# zx81-keyboard.net
KiCad netlist of a schematic drawn in EAGLE
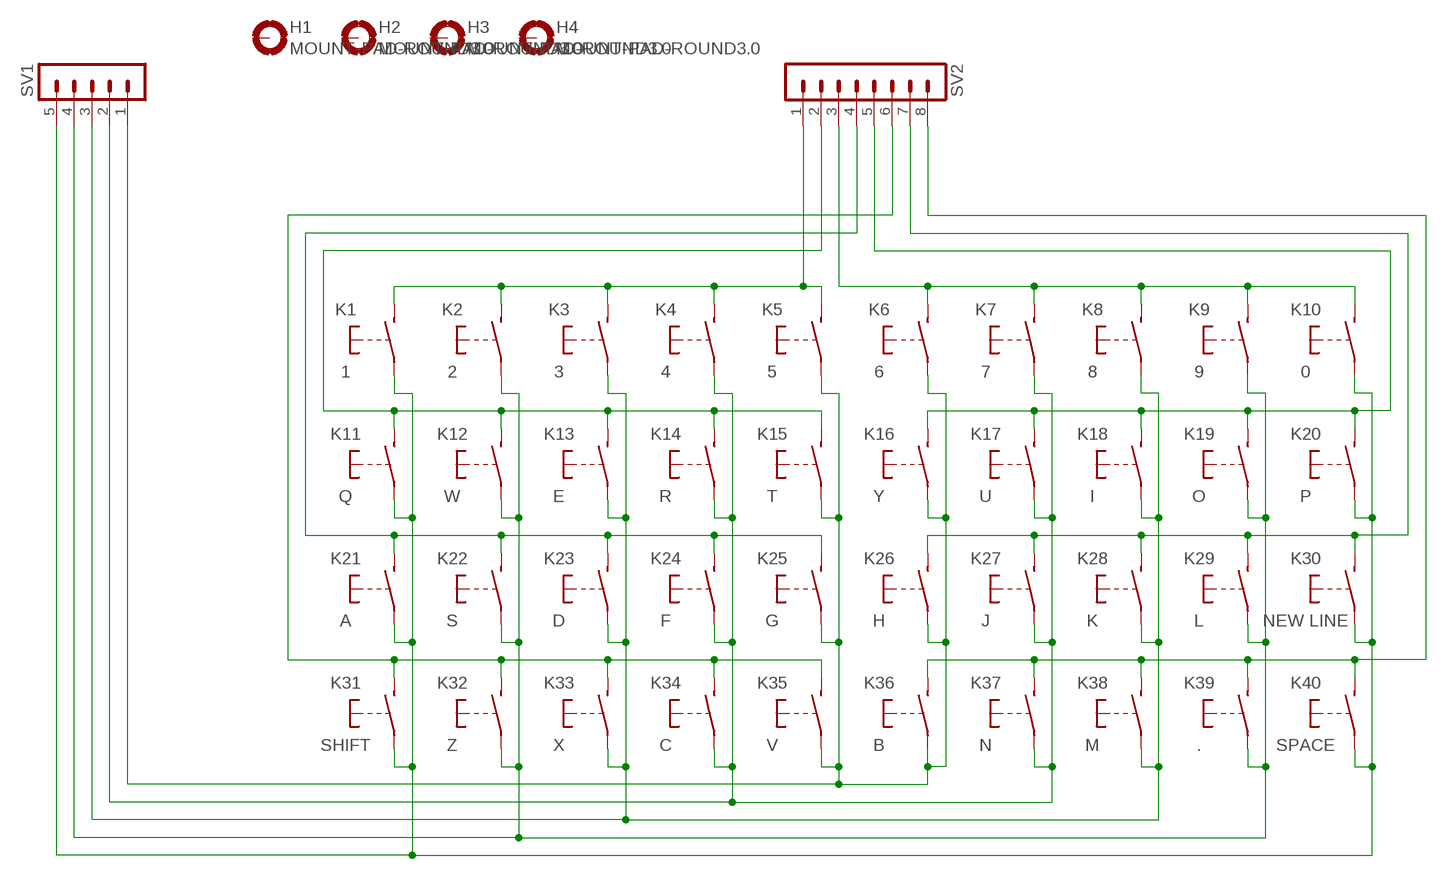
[diagram p0: schematic, sheet 1]

(export (version "E")
  (design (tool "Eeschema 10.0.6"))
  (components
    (comp (ref "H1")
      (value "MOUNT-PAD-ROUND3.0")
      (footprint "eagle-import:3,0-PAD")
      (libsource (lib "eagle-import") (part "MOUNT-PAD-ROUND3.0"))
    )
    (comp (ref "H2")
      (value "MOUNT-PAD-ROUND3.0")
      (footprint "eagle-import:3,0-PAD")
      (libsource (lib "eagle-import") (part "MOUNT-PAD-ROUND3.0"))
    )
    (comp (ref "H3")
      (value "MOUNT-PAD-ROUND3.0")
      (footprint "eagle-import:3,0-PAD")
      (libsource (lib "eagle-import") (part "MOUNT-PAD-ROUND3.0"))
    )
    (comp (ref "H4")
      (value "MOUNT-PAD-ROUND3.0")
      (footprint "eagle-import:3,0-PAD")
      (libsource (lib "eagle-import") (part "MOUNT-PAD-ROUND3.0"))
    )
    (comp (ref "K1")
      (value "1")
      (footprint "eagle-import:MARQUARTDT-6425")
      (libsource (lib "eagle-import") (part "MARQUART-6425"))
    )
    (comp (ref "K2")
      (value "2")
      (footprint "eagle-import:MARQUARTDT-6425")
      (libsource (lib "eagle-import") (part "MARQUART-6425"))
    )
    (comp (ref "K3")
      (value "3")
      (footprint "eagle-import:MARQUARTDT-6425")
      (libsource (lib "eagle-import") (part "MARQUART-6425"))
    )
    (comp (ref "K4")
      (value "4")
      (footprint "eagle-import:MARQUARTDT-6425")
      (libsource (lib "eagle-import") (part "MARQUART-6425"))
    )
    (comp (ref "K5")
      (value "5")
      (footprint "eagle-import:MARQUARTDT-6425")
      (libsource (lib "eagle-import") (part "MARQUART-6425"))
    )
    (comp (ref "K6")
      (value "6")
      (footprint "eagle-import:MARQUARTDT-6425")
      (libsource (lib "eagle-import") (part "MARQUART-6425"))
    )
    (comp (ref "K7")
      (value "7")
      (footprint "eagle-import:MARQUARTDT-6425")
      (libsource (lib "eagle-import") (part "MARQUART-6425"))
    )
    (comp (ref "K8")
      (value "8")
      (footprint "eagle-import:MARQUARTDT-6425")
      (libsource (lib "eagle-import") (part "MARQUART-6425"))
    )
    (comp (ref "K9")
      (value "9")
      (footprint "eagle-import:MARQUARTDT-6425")
      (libsource (lib "eagle-import") (part "MARQUART-6425"))
    )
    (comp (ref "K10")
      (value "0")
      (footprint "eagle-import:MARQUARTDT-6425")
      (libsource (lib "eagle-import") (part "MARQUART-6425"))
    )
    (comp (ref "K11")
      (value "Q")
      (footprint "eagle-import:MARQUARTDT-6425")
      (libsource (lib "eagle-import") (part "MARQUART-6425"))
    )
    (comp (ref "K12")
      (value "W")
      (footprint "eagle-import:MARQUARTDT-6425")
      (libsource (lib "eagle-import") (part "MARQUART-6425"))
    )
    (comp (ref "K13")
      (value "E")
      (footprint "eagle-import:MARQUARTDT-6425")
      (libsource (lib "eagle-import") (part "MARQUART-6425"))
    )
    (comp (ref "K14")
      (value "R")
      (footprint "eagle-import:MARQUARTDT-6425")
      (libsource (lib "eagle-import") (part "MARQUART-6425"))
    )
    (comp (ref "K15")
      (value "T")
      (footprint "eagle-import:MARQUARTDT-6425")
      (libsource (lib "eagle-import") (part "MARQUART-6425"))
    )
    (comp (ref "K16")
      (value "Y")
      (footprint "eagle-import:MARQUARTDT-6425")
      (libsource (lib "eagle-import") (part "MARQUART-6425"))
    )
    (comp (ref "K17")
      (value "U")
      (footprint "eagle-import:MARQUARTDT-6425")
      (libsource (lib "eagle-import") (part "MARQUART-6425"))
    )
    (comp (ref "K18")
      (value "I")
      (footprint "eagle-import:MARQUARTDT-6425")
      (libsource (lib "eagle-import") (part "MARQUART-6425"))
    )
    (comp (ref "K19")
      (value "O")
      (footprint "eagle-import:MARQUARTDT-6425")
      (libsource (lib "eagle-import") (part "MARQUART-6425"))
    )
    (comp (ref "K20")
      (value "P")
      (footprint "eagle-import:MARQUARTDT-6425")
      (libsource (lib "eagle-import") (part "MARQUART-6425"))
    )
    (comp (ref "K21")
      (value "A")
      (footprint "eagle-import:MARQUARTDT-6425")
      (libsource (lib "eagle-import") (part "MARQUART-6425"))
    )
    (comp (ref "K22")
      (value "S")
      (footprint "eagle-import:MARQUARTDT-6425")
      (libsource (lib "eagle-import") (part "MARQUART-6425"))
    )
    (comp (ref "K23")
      (value "D")
      (footprint "eagle-import:MARQUARTDT-6425")
      (libsource (lib "eagle-import") (part "MARQUART-6425"))
    )
    (comp (ref "K24")
      (value "F")
      (footprint "eagle-import:MARQUARTDT-6425")
      (libsource (lib "eagle-import") (part "MARQUART-6425"))
    )
    (comp (ref "K25")
      (value "G")
      (footprint "eagle-import:MARQUARTDT-6425")
      (libsource (lib "eagle-import") (part "MARQUART-6425"))
    )
    (comp (ref "K26")
      (value "H")
      (footprint "eagle-import:MARQUARTDT-6425")
      (libsource (lib "eagle-import") (part "MARQUART-6425"))
    )
    (comp (ref "K27")
      (value "J")
      (footprint "eagle-import:MARQUARTDT-6425")
      (libsource (lib "eagle-import") (part "MARQUART-6425"))
    )
    (comp (ref "K28")
      (value "K")
      (footprint "eagle-import:MARQUARTDT-6425")
      (libsource (lib "eagle-import") (part "MARQUART-6425"))
    )
    (comp (ref "K29")
      (value "L")
      (footprint "eagle-import:MARQUARTDT-6425")
      (libsource (lib "eagle-import") (part "MARQUART-6425"))
    )
    (comp (ref "K30")
      (value "NEW LINE")
      (footprint "eagle-import:MARQUARTDT-6425")
      (libsource (lib "eagle-import") (part "MARQUART-6425"))
    )
    (comp (ref "K31")
      (value "SHIFT")
      (footprint "eagle-import:MARQUARTDT-6425")
      (libsource (lib "eagle-import") (part "MARQUART-6425"))
    )
    (comp (ref "K32")
      (value "Z")
      (footprint "eagle-import:MARQUARTDT-6425")
      (libsource (lib "eagle-import") (part "MARQUART-6425"))
    )
    (comp (ref "K33")
      (value "X")
      (footprint "eagle-import:MARQUARTDT-6425")
      (libsource (lib "eagle-import") (part "MARQUART-6425"))
    )
    (comp (ref "K34")
      (value "C")
      (footprint "eagle-import:MARQUARTDT-6425")
      (libsource (lib "eagle-import") (part "MARQUART-6425"))
    )
    (comp (ref "K35")
      (value "V")
      (footprint "eagle-import:MARQUARTDT-6425")
      (libsource (lib "eagle-import") (part "MARQUART-6425"))
    )
    (comp (ref "K36")
      (value "B")
      (footprint "eagle-import:MARQUARTDT-6425")
      (libsource (lib "eagle-import") (part "MARQUART-6425"))
    )
    (comp (ref "K37")
      (value "N")
      (footprint "eagle-import:MARQUARTDT-6425")
      (libsource (lib "eagle-import") (part "MARQUART-6425"))
    )
    (comp (ref "K38")
      (value "M")
      (footprint "eagle-import:MARQUARTDT-6425")
      (libsource (lib "eagle-import") (part "MARQUART-6425"))
    )
    (comp (ref "K39")
      (value ".")
      (footprint "eagle-import:MARQUARTDT-6425")
      (libsource (lib "eagle-import") (part "MARQUART-6425"))
    )
    (comp (ref "K40")
      (value "SPACE")
      (footprint "eagle-import:MARQUARTDT-6425")
      (libsource (lib "eagle-import") (part "MARQUART-6425"))
    )
    (comp (ref "SV1")
      (value "MA05-1")
      (footprint "eagle-import:MA05-1")
      (libsource (lib "eagle-import") (part "MA05-1"))
    )
    (comp (ref "SV2")
      (value "MA08-1")
      (footprint "eagle-import:MA08-1")
      (libsource (lib "eagle-import") (part "MA08-1"))
    )
  )
  (nets
    (net (code "1") (name "Net-(K1-P)") (class "Default")
      (node (ref "K1") (pin "P$1") (pinfunction "P_P$1") (pintype "passive"))
      (node (ref "K10") (pin "P$1") (pinfunction "P_P$1") (pintype "passive"))
      (node (ref "K11") (pin "P$1") (pinfunction "P_P$1") (pintype "passive"))
      (node (ref "K20") (pin "P$1") (pinfunction "P_P$1") (pintype "passive"))
      (node (ref "K21") (pin "P$1") (pinfunction "P_P$1") (pintype "passive"))
      (node (ref "K30") (pin "P$1") (pinfunction "P_P$1") (pintype "passive"))
      (node (ref "K31") (pin "P$1") (pinfunction "P_P$1") (pintype "passive"))
      (node (ref "K40") (pin "P$1") (pinfunction "P_P$1") (pintype "passive"))
      (node (ref "SV1") (pin "5") (pinfunction "5_5") (pintype "passive"))
    )
    (net (code "2") (name "Net-(K1-S)") (class "Default")
      (node (ref "K1") (pin "P$2") (pinfunction "S_P$2") (pintype "passive"))
      (node (ref "K2") (pin "P$2") (pinfunction "S_P$2") (pintype "passive"))
      (node (ref "K3") (pin "P$2") (pinfunction "S_P$2") (pintype "passive"))
      (node (ref "K4") (pin "P$2") (pinfunction "S_P$2") (pintype "passive"))
      (node (ref "K5") (pin "P$2") (pinfunction "S_P$2") (pintype "passive"))
      (node (ref "SV2") (pin "1") (pinfunction "1_1") (pintype "passive"))
    )
    (net (code "3") (name "Net-(K10-S)") (class "Default")
      (node (ref "K10") (pin "P$2") (pinfunction "S_P$2") (pintype "passive"))
      (node (ref "K6") (pin "P$2") (pinfunction "S_P$2") (pintype "passive"))
      (node (ref "K7") (pin "P$2") (pinfunction "S_P$2") (pintype "passive"))
      (node (ref "K8") (pin "P$2") (pinfunction "S_P$2") (pintype "passive"))
      (node (ref "K9") (pin "P$2") (pinfunction "S_P$2") (pintype "passive"))
      (node (ref "SV2") (pin "3") (pinfunction "3_3") (pintype "passive"))
    )
    (net (code "4") (name "Net-(K11-S)") (class "Default")
      (node (ref "K11") (pin "P$2") (pinfunction "S_P$2") (pintype "passive"))
      (node (ref "K12") (pin "P$2") (pinfunction "S_P$2") (pintype "passive"))
      (node (ref "K13") (pin "P$2") (pinfunction "S_P$2") (pintype "passive"))
      (node (ref "K14") (pin "P$2") (pinfunction "S_P$2") (pintype "passive"))
      (node (ref "K15") (pin "P$2") (pinfunction "S_P$2") (pintype "passive"))
      (node (ref "SV2") (pin "2") (pinfunction "2_2") (pintype "passive"))
    )
    (net (code "5") (name "Net-(K12-P)") (class "Default")
      (node (ref "K12") (pin "P$1") (pinfunction "P_P$1") (pintype "passive"))
      (node (ref "K19") (pin "P$1") (pinfunction "P_P$1") (pintype "passive"))
      (node (ref "K2") (pin "P$1") (pinfunction "P_P$1") (pintype "passive"))
      (node (ref "K22") (pin "P$1") (pinfunction "P_P$1") (pintype "passive"))
      (node (ref "K29") (pin "P$1") (pinfunction "P_P$1") (pintype "passive"))
      (node (ref "K32") (pin "P$1") (pinfunction "P_P$1") (pintype "passive"))
      (node (ref "K39") (pin "P$1") (pinfunction "P_P$1") (pintype "passive"))
      (node (ref "K9") (pin "P$1") (pinfunction "P_P$1") (pintype "passive"))
      (node (ref "SV1") (pin "4") (pinfunction "4_4") (pintype "passive"))
    )
    (net (code "6") (name "Net-(K13-P)") (class "Default")
      (node (ref "K13") (pin "P$1") (pinfunction "P_P$1") (pintype "passive"))
      (node (ref "K18") (pin "P$1") (pinfunction "P_P$1") (pintype "passive"))
      (node (ref "K23") (pin "P$1") (pinfunction "P_P$1") (pintype "passive"))
      (node (ref "K28") (pin "P$1") (pinfunction "P_P$1") (pintype "passive"))
      (node (ref "K3") (pin "P$1") (pinfunction "P_P$1") (pintype "passive"))
      (node (ref "K33") (pin "P$1") (pinfunction "P_P$1") (pintype "passive"))
      (node (ref "K38") (pin "P$1") (pinfunction "P_P$1") (pintype "passive"))
      (node (ref "K8") (pin "P$1") (pinfunction "P_P$1") (pintype "passive"))
      (node (ref "SV1") (pin "3") (pinfunction "3_3") (pintype "passive"))
    )
    (net (code "7") (name "Net-(K14-P)") (class "Default")
      (node (ref "K14") (pin "P$1") (pinfunction "P_P$1") (pintype "passive"))
      (node (ref "K17") (pin "P$1") (pinfunction "P_P$1") (pintype "passive"))
      (node (ref "K24") (pin "P$1") (pinfunction "P_P$1") (pintype "passive"))
      (node (ref "K27") (pin "P$1") (pinfunction "P_P$1") (pintype "passive"))
      (node (ref "K34") (pin "P$1") (pinfunction "P_P$1") (pintype "passive"))
      (node (ref "K37") (pin "P$1") (pinfunction "P_P$1") (pintype "passive"))
      (node (ref "K4") (pin "P$1") (pinfunction "P_P$1") (pintype "passive"))
      (node (ref "K7") (pin "P$1") (pinfunction "P_P$1") (pintype "passive"))
      (node (ref "SV1") (pin "2") (pinfunction "2_2") (pintype "passive"))
    )
    (net (code "8") (name "Net-(K15-P)") (class "Default")
      (node (ref "K15") (pin "P$1") (pinfunction "P_P$1") (pintype "passive"))
      (node (ref "K16") (pin "P$1") (pinfunction "P_P$1") (pintype "passive"))
      (node (ref "K25") (pin "P$1") (pinfunction "P_P$1") (pintype "passive"))
      (node (ref "K26") (pin "P$1") (pinfunction "P_P$1") (pintype "passive"))
      (node (ref "K35") (pin "P$1") (pinfunction "P_P$1") (pintype "passive"))
      (node (ref "K36") (pin "P$1") (pinfunction "P_P$1") (pintype "passive"))
      (node (ref "K5") (pin "P$1") (pinfunction "P_P$1") (pintype "passive"))
      (node (ref "K6") (pin "P$1") (pinfunction "P_P$1") (pintype "passive"))
      (node (ref "SV1") (pin "1") (pinfunction "1_1") (pintype "passive"))
    )
    (net (code "9") (name "Net-(K16-S)") (class "Default")
      (node (ref "K16") (pin "P$2") (pinfunction "S_P$2") (pintype "passive"))
      (node (ref "K17") (pin "P$2") (pinfunction "S_P$2") (pintype "passive"))
      (node (ref "K18") (pin "P$2") (pinfunction "S_P$2") (pintype "passive"))
      (node (ref "K19") (pin "P$2") (pinfunction "S_P$2") (pintype "passive"))
      (node (ref "K20") (pin "P$2") (pinfunction "S_P$2") (pintype "passive"))
      (node (ref "SV2") (pin "5") (pinfunction "5_5") (pintype "passive"))
    )
    (net (code "10") (name "Net-(K21-S)") (class "Default")
      (node (ref "K21") (pin "P$2") (pinfunction "S_P$2") (pintype "passive"))
      (node (ref "K22") (pin "P$2") (pinfunction "S_P$2") (pintype "passive"))
      (node (ref "K23") (pin "P$2") (pinfunction "S_P$2") (pintype "passive"))
      (node (ref "K24") (pin "P$2") (pinfunction "S_P$2") (pintype "passive"))
      (node (ref "K25") (pin "P$2") (pinfunction "S_P$2") (pintype "passive"))
      (node (ref "SV2") (pin "4") (pinfunction "4_4") (pintype "passive"))
    )
    (net (code "11") (name "Net-(K26-S)") (class "Default")
      (node (ref "K26") (pin "P$2") (pinfunction "S_P$2") (pintype "passive"))
      (node (ref "K27") (pin "P$2") (pinfunction "S_P$2") (pintype "passive"))
      (node (ref "K28") (pin "P$2") (pinfunction "S_P$2") (pintype "passive"))
      (node (ref "K29") (pin "P$2") (pinfunction "S_P$2") (pintype "passive"))
      (node (ref "K30") (pin "P$2") (pinfunction "S_P$2") (pintype "passive"))
      (node (ref "SV2") (pin "7") (pinfunction "7_7") (pintype "passive"))
    )
    (net (code "12") (name "Net-(K31-S)") (class "Default")
      (node (ref "K31") (pin "P$2") (pinfunction "S_P$2") (pintype "passive"))
      (node (ref "K32") (pin "P$2") (pinfunction "S_P$2") (pintype "passive"))
      (node (ref "K33") (pin "P$2") (pinfunction "S_P$2") (pintype "passive"))
      (node (ref "K34") (pin "P$2") (pinfunction "S_P$2") (pintype "passive"))
      (node (ref "K35") (pin "P$2") (pinfunction "S_P$2") (pintype "passive"))
      (node (ref "SV2") (pin "6") (pinfunction "6_6") (pintype "passive"))
    )
    (net (code "13") (name "Net-(K36-S)") (class "Default")
      (node (ref "K36") (pin "P$2") (pinfunction "S_P$2") (pintype "passive"))
      (node (ref "K37") (pin "P$2") (pinfunction "S_P$2") (pintype "passive"))
      (node (ref "K38") (pin "P$2") (pinfunction "S_P$2") (pintype "passive"))
      (node (ref "K39") (pin "P$2") (pinfunction "S_P$2") (pintype "passive"))
      (node (ref "K40") (pin "P$2") (pinfunction "S_P$2") (pintype "passive"))
      (node (ref "SV2") (pin "8") (pinfunction "8_8") (pintype "passive"))
    )
    (net (code "14") (name "unconnected-(H1-MOUNT-PadB3,0)") (class "Default")
      (node (ref "H1") (pin "B3,0") (pinfunction "MOUNT_B3,0") (pintype "passive"))
    )
    (net (code "15") (name "unconnected-(H2-MOUNT-PadB3,0)") (class "Default")
      (node (ref "H2") (pin "B3,0") (pinfunction "MOUNT_B3,0") (pintype "passive"))
    )
    (net (code "16") (name "unconnected-(H3-MOUNT-PadB3,0)") (class "Default")
      (node (ref "H3") (pin "B3,0") (pinfunction "MOUNT_B3,0") (pintype "passive"))
    )
    (net (code "17") (name "unconnected-(H4-MOUNT-PadB3,0)") (class "Default")
      (node (ref "H4") (pin "B3,0") (pinfunction "MOUNT_B3,0") (pintype "passive"))
    )
  )
)
